# uARM.net
KiCad netlist of a schematic drawn in Altium Designer
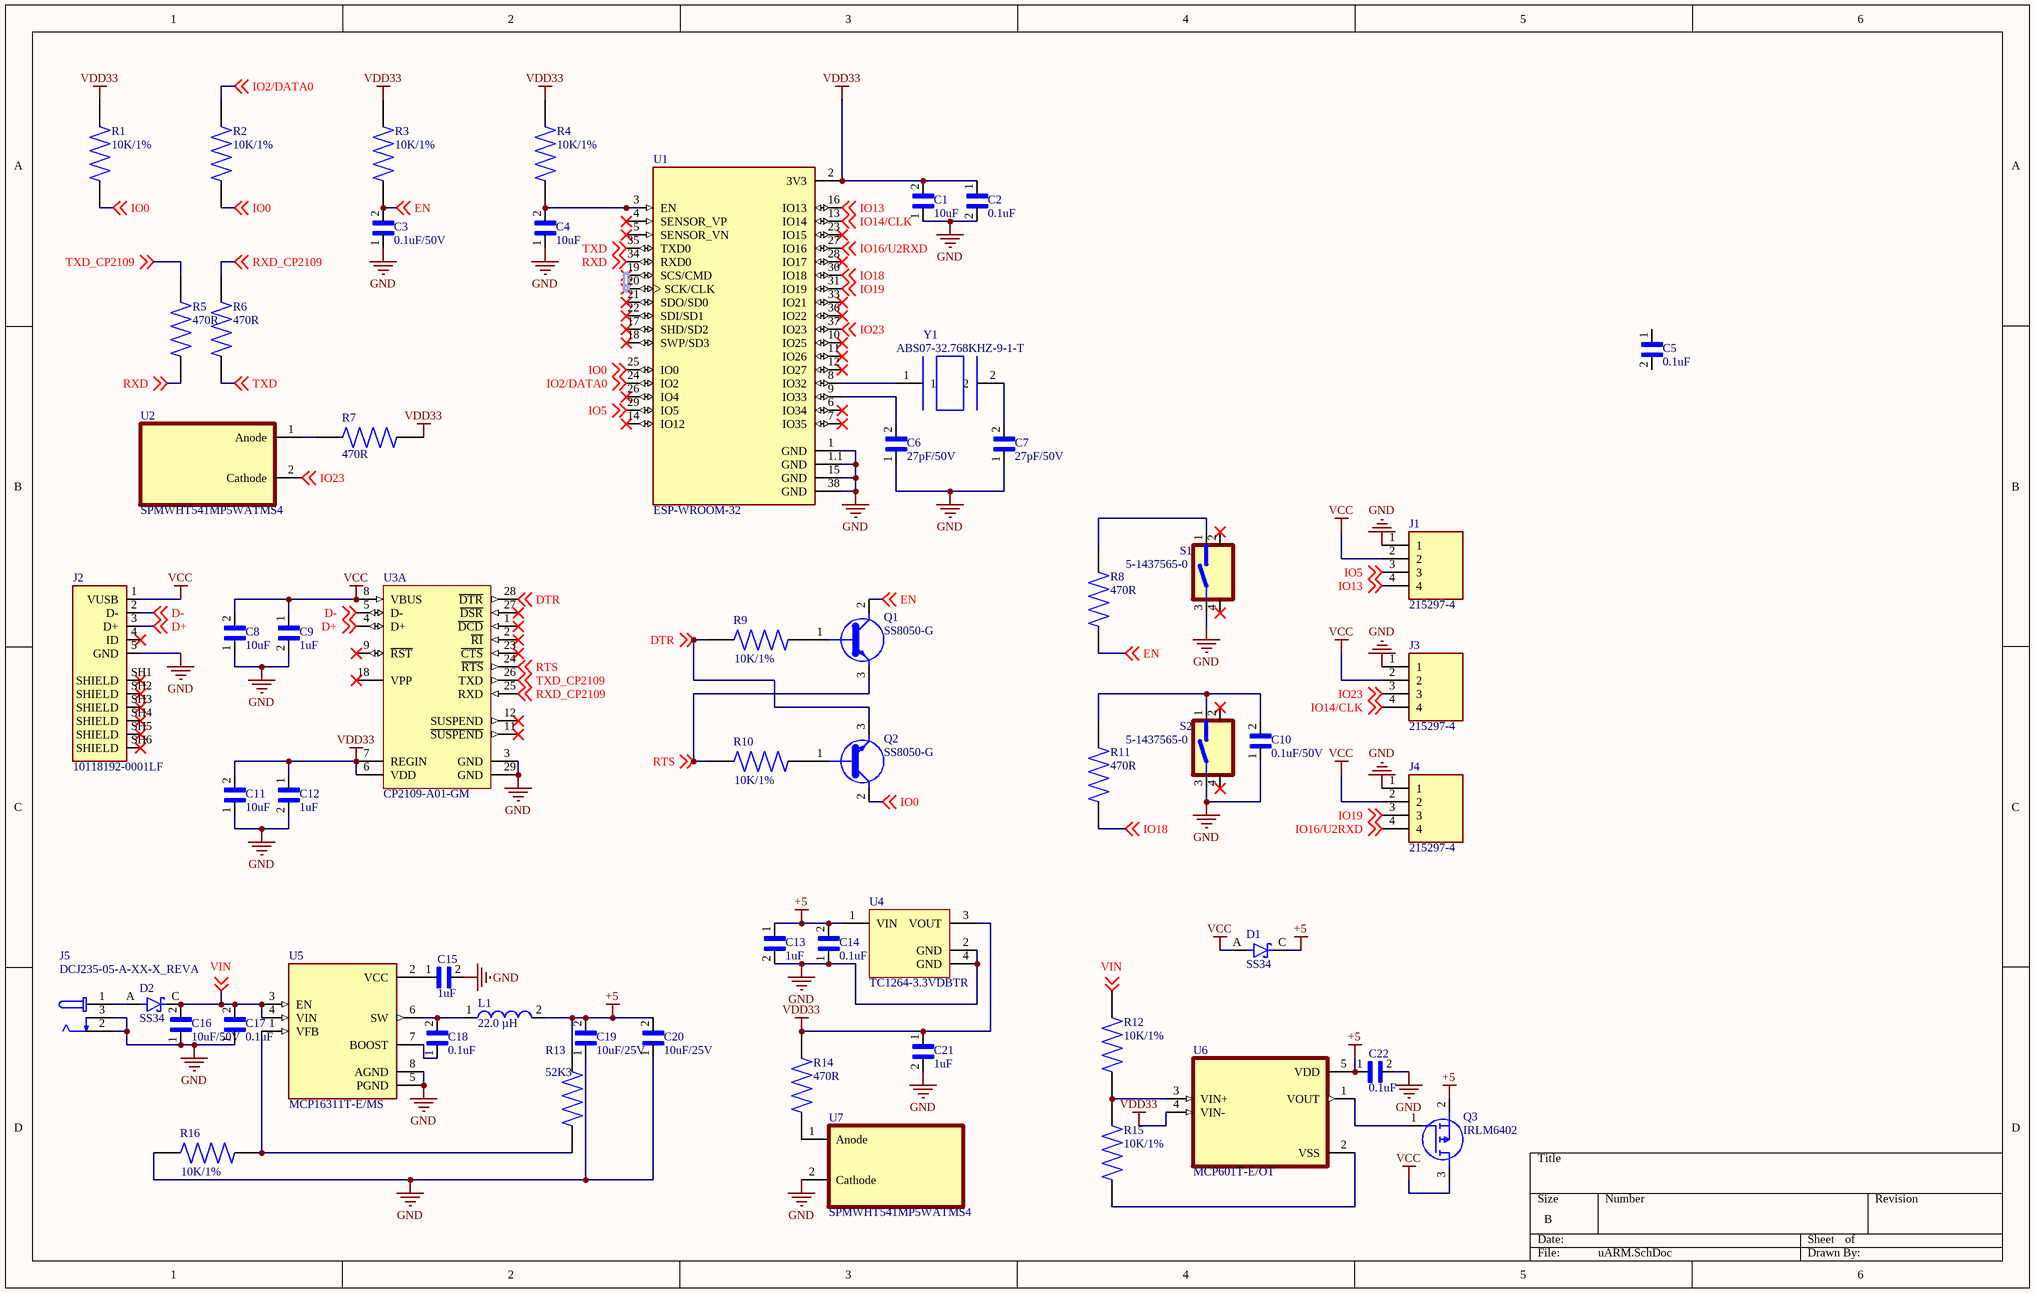
[diagram p0: uARM.SchDoc]

(export (version "E")
  (design (tool "Eeschema 10.0.6"))
  (components
    (comp (ref "C1")
      (value "10uF")
      (footprint "JMK212ABJ106KG-T:CAPC2012X140N")
      (description "CAP CER 10UF 6.3V X5R 0805")
      (fields (field (name "MP") "JMK212ABJ106KG-T") (field (name "MF") "{'manufacturer': u'Taiyo Yuden'}"))
      (libsource (lib "*") (part "JMK212ABJ106KG-T"))
    )
    (comp (ref "C2")
      (value "0.1uF")
      (footprint "08056D104KAT2A:CAPC2012X140N")
      (description "CAP 0.1UF 6.3VDC X5R 10% SMD 0805")
      (fields (field (name "MP") "08056D104KAT2A") (field (name "MF") "{'manufacturer': u'AVX'}"))
      (libsource (lib "") (part "08056D104KAT2A_2"))
    )
    (comp (ref "C3")
      (value "0.1uF/50V")
      (footprint "08055C104KAT4A:CAPC2012X94N")
      (description ".1UF 50V 10% 0805")
      (fields (field (name "MF") "{'manufacturer': u'AVX'}") (field (name "MP") "08055C104KAT4A"))
      (libsource (lib "*") (part "08055C104KAT4A"))
    )
    (comp (ref "C4")
      (value "10uF")
      (footprint "JMK212ABJ106KG-T:CAPC2012X140N")
      (description "CAP CER 10UF 6.3V X5R 0805")
      (fields (field (name "MP") "JMK212ABJ106KG-T") (field (name "MF") "{'manufacturer': u'Taiyo Yuden'}"))
      (libsource (lib "*") (part "JMK212ABJ106KG-T"))
    )
    (comp (ref "C5")
      (value "0.1uF")
      (footprint "08056D104KAT2A:CAPC2012X140N")
      (description "CAP 0.1UF 6.3VDC X5R 10% SMD 0805")
      (fields (field (name "MP") "08056D104KAT2A") (field (name "MF") "{'manufacturer': u'AVX'}"))
      (libsource (lib "") (part "08056D104KAT2A_2"))
    )
    (comp (ref "C6")
      (value "27pF/50V")
      (footprint "C0805C270J5GACTU:CAPC2012X88N")
      (fields (field (name "MP") "C0805C270J5GACTU") (field (name "MF") "{'manufacturer': u'KEMET'}"))
      (libsource (lib "*") (part "C0805C270J5GACTU"))
    )
    (comp (ref "C7")
      (value "27pF/50V")
      (footprint "C0805C270J5GACTU:CAPC2012X88N")
      (fields (field (name "MP") "C0805C270J5GACTU") (field (name "MF") "{'manufacturer': u'KEMET'}"))
      (libsource (lib "*") (part "C0805C270J5GACTU"))
    )
    (comp (ref "C8")
      (value "10uF")
      (footprint "JMK212ABJ106KG-T:CAPC2012X140N")
      (description "CAP CER 10UF 6.3V X5R 0805")
      (fields (field (name "MP") "JMK212ABJ106KG-T") (field (name "MF") "{'manufacturer': u'Taiyo Yuden'}"))
      (libsource (lib "*") (part "JMK212ABJ106KG-T"))
    )
    (comp (ref "C9")
      (value "1uF")
      (footprint "LGC26D105MAT2S1:CAPC2012X140N")
      (description "CAP CER 1UF 6.3V X5R 0805")
      (fields (field (name "MP") "LGC26D105MAT2S1") (field (name "MF") "{'manufacturer': u'AVX'}"))
      (libsource (lib "*") (part "LGC26D105MAT2S1"))
    )
    (comp (ref "C10")
      (value "0.1uF/50V")
      (footprint "08055C104KAT4A:CAPC2012X94N")
      (description ".1UF 50V 10% 0805")
      (fields (field (name "MF") "{'manufacturer': u'AVX'}") (field (name "MP") "08055C104KAT4A"))
      (libsource (lib "*") (part "08055C104KAT4A"))
    )
    (comp (ref "C11")
      (value "10uF")
      (footprint "JMK212ABJ106KG-T:CAPC2012X140N")
      (description "CAP CER 10UF 6.3V X5R 0805")
      (fields (field (name "MP") "JMK212ABJ106KG-T") (field (name "MF") "{'manufacturer': u'Taiyo Yuden'}"))
      (libsource (lib "*") (part "JMK212ABJ106KG-T"))
    )
    (comp (ref "C12")
      (value "1uF")
      (footprint "LGC26D105MAT2S1:CAPC2012X140N")
      (description "CAP CER 1UF 6.3V X5R 0805")
      (fields (field (name "MP") "LGC26D105MAT2S1") (field (name "MF") "{'manufacturer': u'AVX'}"))
      (libsource (lib "*") (part "LGC26D105MAT2S1"))
    )
    (comp (ref "C13")
      (value "1uF")
      (footprint "LGC26D105MAT2S1:CAPC2012X140N")
      (description "CAP CER 1UF 6.3V X5R 0805")
      (fields (field (name "MP") "LGC26D105MAT2S1") (field (name "MF") "{'manufacturer': u'AVX'}"))
      (libsource (lib "*") (part "LGC26D105MAT2S1"))
    )
    (comp (ref "C14")
      (value "0.1uF")
      (footprint "08056D104KAT2A:CAPC2012X140N")
      (description "CAP 0.1UF 6.3VDC X5R 10% SMD 0805")
      (fields (field (name "MP") "08056D104KAT2A") (field (name "MF") "{'manufacturer': u'AVX'}"))
      (libsource (lib "*") (part "08056D104KAT2A"))
    )
    (comp (ref "C15")
      (value "1uF")
      (footprint "LGC26D105MAT2S1:CAPC2012X140N")
      (description "CAP CER 1UF 6.3V X5R 0805")
      (fields (field (name "MP") "LGC26D105MAT2S1") (field (name "MF") "{'manufacturer': u'AVX'}"))
      (libsource (lib "") (part "LGC26D105MAT2S1_1"))
    )
    (comp (ref "C16")
      (value "10uF/50V")
      (footprint "GRM21BR61H106KE43L:CAPC2012X145N")
      (description "SMD Capacitor X5R(EIA) with Capacitance: 10uF Tol. 10%. Rated Voltage: 50Vdc")
      (fields
        (field (name "MP") "GRM21BR61H106KE43L")
        (field (name "MF") "{'manufacturer': u'Murata Electronics'}")
      )
      (libsource (lib "*") (part "GRM21BR61H106KE43L"))
    )
    (comp (ref "C17")
      (value "0.1uF")
      (footprint "08056D104KAT2A:CAPC2012X140N")
      (description "CAP 0.1UF 6.3VDC X5R 10% SMD 0805")
      (fields (field (name "MP") "08056D104KAT2A") (field (name "MF") "{'manufacturer': u'AVX'}"))
      (libsource (lib "*") (part "08056D104KAT2A"))
    )
    (comp (ref "C18")
      (value "0.1uF")
      (footprint "08056D104KAT2A:CAPC2012X140N")
      (description "CAP 0.1UF 6.3VDC X5R 10% SMD 0805")
      (fields (field (name "MP") "08056D104KAT2A") (field (name "MF") "{'manufacturer': u'AVX'}"))
      (libsource (lib "*") (part "08056D104KAT2A"))
    )
    (comp (ref "C19")
      (value "10uF/25V")
      (footprint "CL21A106KAYNNNE:CAPC2012X135N")
      (description "Cap Ceramic 10uF 25V X5R 10% SMD 0805 85Â°C Embossed T/R")
      (fields (field (name "MP") "CL21A106KAYNNNE") (field (name "MF") "{'manufacturer': u'Samsung'}"))
      (libsource (lib "*") (part "CL21A106KAYNNNE"))
    )
    (comp (ref "C20")
      (value "10uF/25V")
      (footprint "CL21A106KAYNNNE:CAPC2012X135N")
      (description "Cap Ceramic 10uF 25V X5R 10% SMD 0805 85Â°C Embossed T/R")
      (fields (field (name "MP") "CL21A106KAYNNNE") (field (name "MF") "{'manufacturer': u'Samsung'}"))
      (libsource (lib "*") (part "CL21A106KAYNNNE"))
    )
    (comp (ref "C21")
      (value "1uF")
      (footprint "LGC26D105MAT2S1:CAPC2012X140N")
      (description "CAP CER 1UF 6.3V X5R 0805")
      (fields (field (name "MP") "LGC26D105MAT2S1") (field (name "MF") "{'manufacturer': u'AVX'}"))
      (libsource (lib "*") (part "LGC26D105MAT2S1"))
    )
    (comp (ref "C22")
      (value "0.1uF")
      (footprint "08056D104KAT2A:CAPC2012X140N")
      (description "CAP 0.1UF 6.3VDC X5R 10% SMD 0805")
      (fields (field (name "MP") "08056D104KAT2A") (field (name "MF") "{'manufacturer': u'AVX'}"))
      (libsource (lib "") (part "08056D104KAT2A_1"))
    )
    (comp (ref "D1")
      (value "SS34")
      (footprint "SS34:DIOM7959X265N")
      (description "Diode Schottky 40V 3A 2-Pin SMC T/R")
      (fields (field (name "MF") "{'manufacturer': u'ON Semiconductor'}"))
      (libsource (lib "*") (part "SS34"))
    )
    (comp (ref "D2")
      (value "SS34")
      (footprint "SS34:DIOM7959X265N")
      (description "Diode Schottky 40V 3A 2-Pin SMC T/R")
      (fields (field (name "MF") "{'manufacturer': u'ON Semiconductor'}"))
      (libsource (lib "*") (part "SS34"))
    )
    (comp (ref "J1")
      (value "215297-4")
      (footprint "215297-4:TE_215297-4")
      (fields (field (name "MF") "{'manufacturer': u'TE Connectivity'}"))
      (libsource (lib "*") (part "215297-4"))
    )
    (comp (ref "J2")
      (value "10118192-0001LF")
      (footprint "10118192-0001LF:AMPHENOL_10118192-0001LF")
      (description "Single Port 5 Contact Horizontal Right Angle Shielded Micro B USB 2.0 Connector")
      (fields (field (name "MF") "{'manufacturer': u'FCI'}"))
      (libsource (lib "*") (part "10118192-0001LF"))
    )
    (comp (ref "J3")
      (value "215297-4")
      (footprint "215297-4:TE_215297-4")
      (fields (field (name "MF") "{'manufacturer': u'TE Connectivity'}"))
      (libsource (lib "*") (part "215297-4"))
    )
    (comp (ref "J4")
      (value "215297-4")
      (footprint "215297-4:TE_215297-4")
      (fields (field (name "MF") "{'manufacturer': u'TE Connectivity'}"))
      (libsource (lib "*") (part "215297-4"))
    )
    (comp (ref "J5")
      (value "DCJ235-05-A-XX-X_REVA")
      (footprint "DCJ235-05-A-K1-A:GCT_DCJ235-05-A-XX-X_REVA")
      (description "DC Power Jack, Thru-Hole, Horizontal, with Locating Pegs, D2.35mm")
      (fields (field (name "MF") "{'manufacturer': u'Global Connector Technology'}"))
      (libsource (lib "*") (part "DCJ235-05-A-XX-X_REVA"))
    )
    (comp (ref "L1")
      (value "744773122")
      (footprint "WE-PD2-S")
      (description "SMD Power Inductor WE-PD2, L = 22.0 µH")
      (fields (field (name "INDUCTANCE") "22.0 µH"))
      (libsource (lib "Wurth_Electronics_744773122") (part "744773122"))
    )
    (comp (ref "Q1")
      (value "SS8050-G")
      (footprint "SS8050-G:MBTB-T-SOT23")
      (fields (field (name "MF") "{'manufacturer': u'Comchip Technology'}"))
      (libsource (lib "*") (part "SS8050-G"))
    )
    (comp (ref "Q2")
      (value "SS8050-G")
      (footprint "SS8050-G:MBTB-T-SOT23")
      (fields (field (name "MF") "{'manufacturer': u'Comchip Technology'}"))
      (libsource (lib "*") (part "SS8050-G"))
    )
    (comp (ref "Q3")
      (value "IRLM6402")
      (footprint "SamacSys:SOT95P237X112-3N")
      (description "MOSFET (P-Channel)")
      (libsource (lib "*") (part "IRLM6402"))
    )
    (comp (ref "R1")
      (value "10K/1%")
      (footprint "ESR10EZPF1002:RESC2012X65N")
      (description "RES SMD 10K OHM 1% 0.4W 0805")
      (fields (field (name "MF") "{'manufacturer': u'Rohm'}") (field (name "MP") "ESR10EZPF1002"))
      (libsource (lib "*") (part "ESR10EZPF1002"))
    )
    (comp (ref "R2")
      (value "10K/1%")
      (footprint "ESR10EZPF1002:RESC2012X65N")
      (description "RES SMD 10K OHM 1% 0.4W 0805")
      (fields (field (name "MF") "{'manufacturer': u'Rohm'}") (field (name "MP") "ESR10EZPF1002"))
      (libsource (lib "*") (part "ESR10EZPF1002"))
    )
    (comp (ref "R3")
      (value "10K/1%")
      (footprint "ESR10EZPF1002:RESC2012X65N")
      (description "RES SMD 10K OHM 1% 0.4W 0805")
      (fields (field (name "MF") "{'manufacturer': u'Rohm'}") (field (name "MP") "ESR10EZPF1002"))
      (libsource (lib "*") (part "ESR10EZPF1002"))
    )
    (comp (ref "R4")
      (value "10K/1%")
      (footprint "ESR10EZPF1002:RESC2012X65N")
      (description "RES SMD 10K OHM 1% 0.4W 0805")
      (fields (field (name "MF") "{'manufacturer': u'Rohm'}") (field (name "MP") "ESR10EZPF1002"))
      (libsource (lib "*") (part "ESR10EZPF1002"))
    )
    (comp (ref "R5")
      (value "470R")
      (footprint "ERJ-PB6B4700V:RESC2012X70N")
      (fields (field (name "MP") "ERJ-PB6B4700V") (field (name "MF") "{'manufacturer': u'Panasonic'}"))
      (libsource (lib "*") (part "ERJ-PB6B4700V"))
    )
    (comp (ref "R6")
      (value "470R")
      (footprint "ERJ-PB6B4700V:RESC2012X70N")
      (fields (field (name "MP") "ERJ-PB6B4700V") (field (name "MF") "{'manufacturer': u'Panasonic'}"))
      (libsource (lib "*") (part "ERJ-PB6B4700V"))
    )
    (comp (ref "R7")
      (value "470R")
      (footprint "ERJ-PB6B4700V:RESC2012X70N")
      (fields (field (name "MP") "ERJ-PB6B4700V") (field (name "MF") "{'manufacturer': u'Panasonic'}"))
      (libsource (lib "*") (part "ERJ-PB6B4700V"))
    )
    (comp (ref "R8")
      (value "470R")
      (footprint "ERJ-PB6B4700V:RESC2012X70N")
      (fields (field (name "MP") "ERJ-PB6B4700V") (field (name "MF") "{'manufacturer': u'Panasonic'}"))
      (libsource (lib "*") (part "ERJ-PB6B4700V"))
    )
    (comp (ref "R9")
      (value "10K/1%")
      (footprint "ESR10EZPF1002:RESC2012X65N")
      (description "RES SMD 10K OHM 1% 0.4W 0805")
      (fields (field (name "MF") "{'manufacturer': u'Rohm'}") (field (name "MP") "ESR10EZPF1002"))
      (libsource (lib "*") (part "ESR10EZPF1002"))
    )
    (comp (ref "R10")
      (value "10K/1%")
      (footprint "ESR10EZPF1002:RESC2012X65N")
      (description "RES SMD 10K OHM 1% 0.4W 0805")
      (fields (field (name "MF") "{'manufacturer': u'Rohm'}") (field (name "MP") "ESR10EZPF1002"))
      (libsource (lib "*") (part "ESR10EZPF1002"))
    )
    (comp (ref "R11")
      (value "470R")
      (footprint "ERJ-PB6B4700V:RESC2012X70N")
      (fields (field (name "MP") "ERJ-PB6B4700V") (field (name "MF") "{'manufacturer': u'Panasonic'}"))
      (libsource (lib "*") (part "ERJ-PB6B4700V"))
    )
    (comp (ref "R12")
      (value "10K/1%")
      (footprint "ESR10EZPF1002:RESC2012X65N")
      (description "RES SMD 10K OHM 1% 0.4W 0805")
      (fields (field (name "MF") "{'manufacturer': u'Rohm'}") (field (name "MP") "ESR10EZPF1002"))
      (libsource (lib "*") (part "ESR10EZPF1002"))
    )
    (comp (ref "R13")
      (value "52K3")
      (footprint "ERJ-1GEF5232C:RESC0603X26N")
      (description "Res Thick Film 0201 52.3K Ohm 1% 0.05W(1/20W) Â±200ppm/C SMD T/R")
      (fields (field (name "MP") "ERJ-1GEF5232C") (field (name "MF") "{'manufacturer': u'Panasonic'}"))
      (libsource (lib "*") (part "ERJ-1GEF5232C"))
    )
    (comp (ref "R14")
      (value "470R")
      (footprint "ERJ-PB6B4700V:RESC2012X70N")
      (fields (field (name "MP") "ERJ-PB6B4700V") (field (name "MF") "{'manufacturer': u'Panasonic'}"))
      (libsource (lib "*") (part "ERJ-PB6B4700V"))
    )
    (comp (ref "R15")
      (value "10K/1%")
      (footprint "ESR10EZPF1002:RESC2012X65N")
      (description "RES SMD 10K OHM 1% 0.4W 0805")
      (fields (field (name "MF") "{'manufacturer': u'Rohm'}") (field (name "MP") "ESR10EZPF1002"))
      (libsource (lib "*") (part "ESR10EZPF1002"))
    )
    (comp (ref "R16")
      (value "10K/1%")
      (footprint "ESR10EZPF1002:RESC2012X65N")
      (description "RES SMD 10K OHM 1% 0.4W 0805")
      (fields (field (name "MF") "{'manufacturer': u'Rohm'}") (field (name "MP") "ESR10EZPF1002"))
      (libsource (lib "*") (part "ESR10EZPF1002"))
    )
    (comp (ref "S1")
      (value "5-1437565-0")
      (footprint "FSM6JSMATR:SW_5-1437565-0")
      (description "Switch Tactile OFF (ON) Round Button Gull Wing 0.05A 12VDC 1.57N SMD T/R")
      (fields (field (name "MF") "{'manufacturer': u'TE Connectivity'}"))
      (libsource (lib "*") (part "5-1437565-0"))
    )
    (comp (ref "S2")
      (value "5-1437565-0")
      (footprint "FSM6JSMATR:SW_5-1437565-0")
      (description "Switch Tactile OFF (ON) Round Button Gull Wing 0.05A 12VDC 1.57N SMD T/R")
      (fields (field (name "MF") "{'manufacturer': u'TE Connectivity'}"))
      (libsource (lib "*") (part "5-1437565-0"))
    )
    (comp (ref "U1")
      (value "ESP-WROOM-32")
      (footprint "ESP-WROOM-32:MODULE_ESP-WROOM-32")
      (description "Module: combo; GPIO, I2C x2, I2S x2, SDIO, SPI x3, UART x3; 19.5dBm")
      (fields (field (name "MF") "{'manufacturer': u'Espressif Systems'}"))
      (libsource (lib "*") (part "ESP-WROOM-32"))
    )
    (comp (ref "U2")
      (value "SPMWHT541MP5WATMS4")
      (footprint "LED_SPMWHT541MP5WAPKS4")
      (fields (field (name "MF") "{'manufacturer': u'Samsung Semiconductor,'}"))
      (libsource (lib "uARM") (part "SPMWHT541MP5WATMS4"))
    )
    (comp (ref "U3")
      (value "CP2109-A01-GM")
      (footprint "SLAB-QFN-28-3125x3125TP_L")
      (description "Single-Chip USB to UART Bridge, 1024 Bytes EEPROM, -40 to 85 degC, 28-pin QFN, Tube")
      (fields (field (name "MANUFACTURER") "Silicon Labs"))
      (libsource (lib "Silicon_Labs_CP2109_A01_GM") (part "CP2109-A01-GM"))
    )
    (comp (ref "U4")
      (value "TC1264-3.3VDBTR")
      (footprint "SOT-223-DB3_L")
      (description "800 mA Fixed-Output CMOS LDO with Shutdown, 3-Pin SOT-223, Extended Temperature, Tape and Reel")
      (libsource (lib "Microchip_TC1264_3_3VDBTR") (part "TC1264-3.3VDBTR"))
    )
    (comp (ref "U5")
      (value "MCP16311T-E/MS")
      (footprint "MCP16311T-E_MS:SOP65P490X110-8N")
      (fields (field (name "MF") "{'manufacturer': u'Microchip Technology'}"))
      (libsource (lib "*") (part "MCP16311T-E/MS"))
    )
    (comp (ref "U6")
      (value "MCP601T-E/OT")
      (footprint "MCP601T-E_OT:SOT95P270X145-5N")
      (fields (field (name "MF") "{'manufacturer': u'Microchip'}"))
      (libsource (lib "*") (part "MCP601T-E/OT"))
    )
    (comp (ref "U7")
      (value "SPMWHT541MP5WATMS4")
      (footprint "SPMWHT541MP5WATMS4:LED_SPMWHT541MP5WAPKS4")
      (fields (field (name "MF") "{'manufacturer': u'Samsung Semiconductor,'}"))
      (libsource (lib "*") (part "SPMWHT541MP5WATMS4"))
    )
    (comp (ref "Y1")
      (value "ABS07-32.768KHZ-9-1-T")
      (footprint "ABS07-32.768KHZ-9-1-T:XTAL320X150X90")
      (description "ABS07 Series 32.768 kHz Â±20 ppm 12.5 pF -40 to +85 C SMT Low Profile Crystal")
      (fields (field (name "MF") "{'manufacturer': u'Abracon'}"))
      (libsource (lib "*") (part "ABS07-32.768KHZ-9-1-T"))
    )
  )
  (nets
    (net (code "1") (name "+5") (class "Default")
      (node (ref "C13") (pin "1") (pinfunction "1_1") (pintype "passive"))
      (node (ref "C14") (pin "2") (pinfunction "2_2") (pintype "passive"))
      (node (ref "C19") (pin "2") (pinfunction "2_2") (pintype "passive"))
      (node (ref "C20") (pin "2") (pinfunction "2_2") (pintype "passive"))
      (node (ref "C22") (pin "1") (pinfunction "1_1") (pintype "passive"))
      (node (ref "D1") (pin "C") (pinfunction "K_C") (pintype "passive"))
      (node (ref "L1") (pin "2") (pinfunction "2_2") (pintype "passive"))
      (node (ref "Q3") (pin "2") (pinfunction "S_2") (pintype "passive"))
      (node (ref "R13") (pin "2") (pinfunction "2_2") (pintype "passive"))
      (node (ref "U4") (pin "1") (pinfunction "VIN_1") (pintype "power_in"))
      (node (ref "U6") (pin "5") (pinfunction "VDD_5") (pintype "power_in"))
    )
    (net (code "2") (name "D+") (class "Default")
      (node (ref "J2") (pin "3") (pinfunction "D+_3") (pintype "passive"))
      (node (ref "U3") (pin "4") (pinfunction "D+_4") (pintype "bidirectional"))
    )
    (net (code "3") (name "D-") (class "Default")
      (node (ref "J2") (pin "2") (pinfunction "D-_2") (pintype "passive"))
      (node (ref "U3") (pin "5") (pinfunction "D-_5") (pintype "bidirectional"))
    )
    (net (code "4") (name "DTR") (class "Default")
      (node (ref "Q2") (pin "3") (pinfunction "C_3") (pintype "bidirectional"))
      (node (ref "R9") (pin "1") (pinfunction "1_1") (pintype "passive"))
      (node (ref "U3") (pin "28") (pinfunction "~{DTR}_28") (pintype "output"))
    )
    (net (code "5") (name "EN") (class "Default")
      (node (ref "C3") (pin "2") (pinfunction "2_2") (pintype "passive"))
      (node (ref "Q1") (pin "2") (pinfunction "E_2") (pintype "bidirectional"))
      (node (ref "R3") (pin "1") (pinfunction "1_1") (pintype "passive"))
      (node (ref "R8") (pin "1") (pinfunction "1_1") (pintype "passive"))
    )
    (net (code "6") (name "GND") (class "Default")
      (node (ref "C1") (pin "1") (pinfunction "1_1") (pintype "passive"))
      (node (ref "C10") (pin "1") (pinfunction "1_1") (pintype "passive"))
      (node (ref "C11") (pin "1") (pinfunction "1_1") (pintype "passive"))
      (node (ref "C12") (pin "2") (pinfunction "2_2") (pintype "passive"))
      (node (ref "C13") (pin "2") (pinfunction "2_2") (pintype "passive"))
      (node (ref "C14") (pin "1") (pinfunction "1_1") (pintype "passive"))
      (node (ref "C15") (pin "2") (pinfunction "2_2") (pintype "passive"))
      (node (ref "C16") (pin "1") (pinfunction "1_1") (pintype "passive"))
      (node (ref "C17") (pin "1") (pinfunction "1_1") (pintype "passive"))
      (node (ref "C19") (pin "1") (pinfunction "1_1") (pintype "passive"))
      (node (ref "C2") (pin "2") (pinfunction "2_2") (pintype "passive"))
      (node (ref "C20") (pin "1") (pinfunction "1_1") (pintype "passive"))
      (node (ref "C21") (pin "2") (pinfunction "2_2") (pintype "passive"))
      (node (ref "C22") (pin "2") (pinfunction "2_2") (pintype "passive"))
      (node (ref "C3") (pin "1") (pinfunction "1_1") (pintype "passive"))
      (node (ref "C4") (pin "1") (pinfunction "1_1") (pintype "passive"))
      (node (ref "C6") (pin "1") (pinfunction "1_1") (pintype "passive"))
      (node (ref "C7") (pin "1") (pinfunction "1_1") (pintype "passive"))
      (node (ref "C8") (pin "1") (pinfunction "1_1") (pintype "passive"))
      (node (ref "C9") (pin "2") (pinfunction "2_2") (pintype "passive"))
      (node (ref "J1") (pin "1") (pinfunction "1_1") (pintype "passive"))
      (node (ref "J2") (pin "5") (pinfunction "GND_5") (pintype "passive"))
      (node (ref "J3") (pin "1") (pinfunction "1_1") (pintype "passive"))
      (node (ref "J4") (pin "1") (pinfunction "1_1") (pintype "passive"))
      (node (ref "J5") (pin "2") (pinfunction "2_2") (pintype "passive"))
      (node (ref "J5") (pin "3") (pinfunction "3_3") (pintype "passive"))
      (node (ref "R16") (pin "1") (pinfunction "1_1") (pintype "passive"))
      (node (ref "S1") (pin "3") (pinfunction "1_3") (pintype "passive"))
      (node (ref "S2") (pin "3") (pinfunction "1_3") (pintype "passive"))
      (node (ref "U1") (pin "1") (pinfunction "GND_1") (pintype "power_in"))
      (node (ref "U1") (pin "1.1") (pinfunction "GND_1.1") (pintype "power_in"))
      (node (ref "U1") (pin "15") (pinfunction "GND_15") (pintype "power_in"))
      (node (ref "U1") (pin "38") (pinfunction "GND_38") (pintype "power_in"))
      (node (ref "U3") (pin "29") (pinfunction "GND_29") (pintype "power_in"))
      (node (ref "U3") (pin "3") (pinfunction "GND_3") (pintype "power_in"))
      (node (ref "U4") (pin "2") (pinfunction "GND_2") (pintype "power_in"))
      (node (ref "U4") (pin "4") (pinfunction "GND_4") (pintype "power_in"))
      (node (ref "U5") (pin "5") (pinfunction "PGND_5") (pintype "power_in"))
      (node (ref "U5") (pin "8") (pinfunction "AGND_8") (pintype "power_in"))
      (node (ref "U7") (pin "2") (pinfunction "Cathode_2") (pintype "power_in"))
    )
    (net (code "7") (name "IO0") (class "Default")
      (node (ref "Q2") (pin "2") (pinfunction "E_2") (pintype "bidirectional"))
      (node (ref "R1") (pin "1") (pinfunction "1_1") (pintype "passive"))
      (node (ref "R2") (pin "1") (pinfunction "1_1") (pintype "passive"))
      (node (ref "U1") (pin "25") (pinfunction "IO0_25") (pintype "bidirectional"))
    )
    (net (code "8") (name "IO2{slash}DATA0") (class "Default")
      (node (ref "R2") (pin "2") (pinfunction "2_2") (pintype "passive"))
      (node (ref "U1") (pin "24") (pinfunction "IO2_24") (pintype "bidirectional"))
    )
    (net (code "9") (name "IO5") (class "Default")
      (node (ref "J1") (pin "3") (pinfunction "3_3") (pintype "passive"))
      (node (ref "U1") (pin "29") (pinfunction "IO5_29") (pintype "bidirectional"))
    )
    (net (code "10") (name "IO13") (class "Default")
      (node (ref "J1") (pin "4") (pinfunction "4_4") (pintype "passive"))
      (node (ref "U1") (pin "16") (pinfunction "IO13_16") (pintype "bidirectional"))
    )
    (net (code "11") (name "IO14{slash}CLK") (class "Default")
      (node (ref "J3") (pin "4") (pinfunction "4_4") (pintype "passive"))
      (node (ref "U1") (pin "13") (pinfunction "IO14_13") (pintype "bidirectional"))
    )
    (net (code "12") (name "IO16{slash}U2RXD") (class "Default")
      (node (ref "J4") (pin "4") (pinfunction "4_4") (pintype "passive"))
      (node (ref "U1") (pin "27") (pinfunction "IO16_27") (pintype "bidirectional"))
    )
    (net (code "13") (name "IO18") (class "Default")
      (node (ref "R11") (pin "1") (pinfunction "1_1") (pintype "passive"))
      (node (ref "U1") (pin "30") (pinfunction "IO18_30") (pintype "bidirectional"))
    )
    (net (code "14") (name "IO19") (class "Default")
      (node (ref "J4") (pin "3") (pinfunction "3_3") (pintype "passive"))
      (node (ref "U1") (pin "31") (pinfunction "IO19_31") (pintype "bidirectional"))
    )
    (net (code "15") (name "IO23") (class "Default")
      (node (ref "J3") (pin "3") (pinfunction "3_3") (pintype "passive"))
      (node (ref "U1") (pin "37") (pinfunction "IO23_37") (pintype "bidirectional"))
      (node (ref "U2") (pin "2") (pinfunction "Cathode_2") (pintype "power_in"))
    )
    (net (code "16") (name "Net-(C7-Pad2)") (class "Default")
      (node (ref "C7") (pin "2") (pinfunction "2_2") (pintype "passive"))
      (node (ref "Y1") (pin "2") (pinfunction "2_2") (pintype "passive"))
    )
    (net (code "17") (name "Net-(C10-Pad2)") (class "Default")
      (node (ref "C10") (pin "2") (pinfunction "2_2") (pintype "passive"))
      (node (ref "R11") (pin "2") (pinfunction "2_2") (pintype "passive"))
      (node (ref "S2") (pin "1") (pinfunction "2_1") (pintype "passive"))
    )
    (net (code "18") (name "Net-(D2-PadA)") (class "Default")
      (node (ref "D2") (pin "A") (pinfunction "A_A") (pintype "passive"))
      (node (ref "J5") (pin "1") (pinfunction "1_1") (pintype "passive"))
    )
    (net (code "19") (name "Net-(Q1-B)") (class "Default")
      (node (ref "Q1") (pin "1") (pinfunction "B_1") (pintype "bidirectional"))
      (node (ref "R9") (pin "2") (pinfunction "2_2") (pintype "passive"))
    )
    (net (code "20") (name "Net-(Q2-B)") (class "Default")
      (node (ref "Q2") (pin "1") (pinfunction "B_1") (pintype "bidirectional"))
      (node (ref "R10") (pin "2") (pinfunction "2_2") (pintype "passive"))
    )
    (net (code "21") (name "Net-(Q3-G)") (class "Default")
      (node (ref "Q3") (pin "1") (pinfunction "G_1") (pintype "passive"))
      (node (ref "U6") (pin "1") (pinfunction "VOUT_1") (pintype "output"))
    )
    (net (code "22") (name "Net-(R8-Pad2)") (class "Default")
      (node (ref "R8") (pin "2") (pinfunction "2_2") (pintype "passive"))
      (node (ref "S1") (pin "1") (pinfunction "2_1") (pintype "passive"))
    )
    (net (code "23") (name "Net-(U1-EN)") (class "Default")
      (node (ref "C4") (pin "2") (pinfunction "2_2") (pintype "passive"))
      (node (ref "R4") (pin "1") (pinfunction "1_1") (pintype "passive"))
      (node (ref "U1") (pin "3") (pinfunction "EN_3") (pintype "input"))
    )
    (net (code "24") (name "Net-(U1-IO32)") (class "Default")
      (node (ref "U1") (pin "8") (pinfunction "IO32_8") (pintype "bidirectional"))
      (node (ref "Y1") (pin "1") (pinfunction "1_1") (pintype "passive"))
    )
    (net (code "25") (name "Net-(U1-IO33)") (class "Default")
      (node (ref "C6") (pin "2") (pinfunction "2_2") (pintype "passive"))
      (node (ref "U1") (pin "9") (pinfunction "IO33_9") (pintype "bidirectional"))
    )
    (net (code "26") (name "Net-(U2-Anode)") (class "Default")
      (node (ref "R7") (pin "2") (pinfunction "2_2") (pintype "passive"))
      (node (ref "U2") (pin "1") (pinfunction "Anode_1") (pintype "power_in"))
    )
    (net (code "27") (name "Net-(U5-BOOST)") (class "Default")
      (node (ref "C18") (pin "1") (pinfunction "1_1") (pintype "passive"))
      (node (ref "U5") (pin "7") (pinfunction "BOOST_7") (pintype "passive"))
    )
    (net (code "28") (name "Net-(U5-SW)") (class "Default")
      (node (ref "C18") (pin "2") (pinfunction "2_2") (pintype "passive"))
      (node (ref "L1") (pin "1") (pinfunction "1_1") (pintype "passive"))
      (node (ref "U5") (pin "6") (pinfunction "SW_6") (pintype "output"))
    )
    (net (code "29") (name "Net-(U5-VCC)") (class "Default")
      (node (ref "C15") (pin "1") (pinfunction "1_1") (pintype "passive"))
      (node (ref "U5") (pin "2") (pinfunction "VCC_2") (pintype "power_in"))
    )
    (net (code "30") (name "Net-(U5-VFB)") (class "Default")
      (node (ref "R13") (pin "1") (pinfunction "1_1") (pintype "passive"))
      (node (ref "R16") (pin "2") (pinfunction "2_2") (pintype "passive"))
      (node (ref "U5") (pin "1") (pinfunction "VFB_1") (pintype "input"))
    )
    (net (code "31") (name "Net-(U6-VIN+)") (class "Default")
      (node (ref "R12") (pin "1") (pinfunction "1_1") (pintype "passive"))
      (node (ref "R15") (pin "2") (pinfunction "2_2") (pintype "passive"))
      (node (ref "U6") (pin "3") (pinfunction "VIN+_3") (pintype "input"))
    )
    (net (code "32") (name "Net-(U6-VSS)") (class "Default")
      (node (ref "R15") (pin "1") (pinfunction "1_1") (pintype "passive"))
      (node (ref "U6") (pin "2") (pinfunction "VSS_2") (pintype "power_in"))
    )
    (net (code "33") (name "Net-(U7-Anode)") (class "Default")
      (node (ref "R14") (pin "1") (pinfunction "1_1") (pintype "passive"))
      (node (ref "U7") (pin "1") (pinfunction "Anode_1") (pintype "power_in"))
    )
    (net (code "34") (name "RTS") (class "Default")
      (node (ref "Q1") (pin "3") (pinfunction "C_3") (pintype "bidirectional"))
      (node (ref "R10") (pin "1") (pinfunction "1_1") (pintype "passive"))
      (node (ref "U3") (pin "24") (pinfunction "~{RTS}_24") (pintype "output"))
    )
    (net (code "35") (name "RXD") (class "Default")
      (node (ref "R5") (pin "1") (pinfunction "1_1") (pintype "passive"))
      (node (ref "U1") (pin "34") (pinfunction "RXD0_34") (pintype "bidirectional"))
    )
    (net (code "36") (name "RXD_CP2109") (class "Default")
      (node (ref "R6") (pin "2") (pinfunction "2_2") (pintype "passive"))
      (node (ref "U3") (pin "25") (pinfunction "RXD_25") (pintype "input"))
    )
    (net (code "37") (name "TXD") (class "Default")
      (node (ref "R6") (pin "1") (pinfunction "1_1") (pintype "passive"))
      (node (ref "U1") (pin "35") (pinfunction "TXD0_35") (pintype "bidirectional"))
    )
    (net (code "38") (name "TXD_CP2109") (class "Default")
      (node (ref "R5") (pin "2") (pinfunction "2_2") (pintype "passive"))
      (node (ref "U3") (pin "26") (pinfunction "TXD_26") (pintype "output"))
    )
    (net (code "39") (name "VCC") (class "Default")
      (node (ref "C8") (pin "2") (pinfunction "2_2") (pintype "passive"))
      (node (ref "C9") (pin "1") (pinfunction "1_1") (pintype "passive"))
      (node (ref "D1") (pin "A") (pinfunction "A_A") (pintype "passive"))
      (node (ref "J1") (pin "2") (pinfunction "2_2") (pintype "passive"))
      (node (ref "J2") (pin "1") (pinfunction "VUSB_1") (pintype "passive"))
      (node (ref "J3") (pin "2") (pinfunction "2_2") (pintype "passive"))
      (node (ref "J4") (pin "2") (pinfunction "2_2") (pintype "passive"))
      (node (ref "Q3") (pin "3") (pinfunction "D_3") (pintype "passive"))
      (node (ref "U3") (pin "8") (pinfunction "VBUS_8") (pintype "input"))
    )
    (net (code "40") (name "VDD33") (class "Default")
      (node (ref "C1") (pin "2") (pinfunction "2_2") (pintype "passive"))
      (node (ref "C11") (pin "2") (pinfunction "2_2") (pintype "passive"))
      (node (ref "C12") (pin "1") (pinfunction "1_1") (pintype "passive"))
      (node (ref "C2") (pin "1") (pinfunction "1_1") (pintype "passive"))
      (node (ref "C21") (pin "1") (pinfunction "1_1") (pintype "passive"))
      (node (ref "R1") (pin "2") (pinfunction "2_2") (pintype "passive"))
      (node (ref "R14") (pin "2") (pinfunction "2_2") (pintype "passive"))
      (node (ref "R3") (pin "2") (pinfunction "2_2") (pintype "passive"))
      (node (ref "R4") (pin "2") (pinfunction "2_2") (pintype "passive"))
      (node (ref "R7") (pin "1") (pinfunction "1_1") (pintype "passive"))
      (node (ref "U1") (pin "2") (pinfunction "3V3_2") (pintype "power_in"))
      (node (ref "U3") (pin "6") (pinfunction "VDD_6") (pintype "power_in"))
      (node (ref "U3") (pin "7") (pinfunction "REGIN_7") (pintype "power_in"))
      (node (ref "U4") (pin "3") (pinfunction "VOUT_3") (pintype "power_in"))
      (node (ref "U6") (pin "4") (pinfunction "VIN-_4") (pintype "input"))
    )
    (net (code "41") (name "VIN") (class "Default")
      (node (ref "C16") (pin "2") (pinfunction "2_2") (pintype "passive"))
      (node (ref "C17") (pin "2") (pinfunction "2_2") (pintype "passive"))
      (node (ref "D2") (pin "C") (pinfunction "K_C") (pintype "passive"))
      (node (ref "R12") (pin "2") (pinfunction "2_2") (pintype "passive"))
      (node (ref "U5") (pin "3") (pinfunction "EN_3") (pintype "input"))
      (node (ref "U5") (pin "4") (pinfunction "VIN_4") (pintype "input"))
    )
    (net (code "42") (name "unconnected-(C5-Pad1)") (class "Default")
      (node (ref "C5") (pin "1") (pinfunction "1_1") (pintype "passive"))
    )
    (net (code "43") (name "unconnected-(C5-Pad2)") (class "Default")
      (node (ref "C5") (pin "2") (pinfunction "2_2") (pintype "passive"))
    )
    (net (code "44") (name "unconnected-(J2-ID-Pad4)") (class "Default")
      (node (ref "J2") (pin "4") (pinfunction "ID_4") (pintype "passive+no_connect"))
    )
    (net (code "45") (name "unconnected-(J2-SHIELD-PadSH1)") (class "Default")
      (node (ref "J2") (pin "SH1") (pinfunction "SHIELD_SH1") (pintype "passive+no_connect"))
    )
    (net (code "46") (name "unconnected-(J2-SHIELD-PadSH2)") (class "Default")
      (node (ref "J2") (pin "SH2") (pinfunction "SHIELD_SH2") (pintype "passive+no_connect"))
    )
    (net (code "47") (name "unconnected-(J2-SHIELD-PadSH3)") (class "Default")
      (node (ref "J2") (pin "SH3") (pinfunction "SHIELD_SH3") (pintype "passive+no_connect"))
    )
    (net (code "48") (name "unconnected-(J2-SHIELD-PadSH4)") (class "Default")
      (node (ref "J2") (pin "SH4") (pinfunction "SHIELD_SH4") (pintype "passive+no_connect"))
    )
    (net (code "49") (name "unconnected-(J2-SHIELD-PadSH5)") (class "Default")
      (node (ref "J2") (pin "SH5") (pinfunction "SHIELD_SH5") (pintype "passive+no_connect"))
    )
    (net (code "50") (name "unconnected-(J2-SHIELD-PadSH6)") (class "Default")
      (node (ref "J2") (pin "SH6") (pinfunction "SHIELD_SH6") (pintype "passive+no_connect"))
    )
    (net (code "51") (name "unconnected-(S1-1-Pad4)") (class "Default")
      (node (ref "S1") (pin "4") (pinfunction "1_4") (pintype "passive+no_connect"))
    )
    (net (code "52") (name "unconnected-(S1-Pad2)") (class "Default")
      (node (ref "S1") (pin "2") (pinfunction "2_2") (pintype "passive+no_connect"))
    )
    (net (code "53") (name "unconnected-(S2-1-Pad4)") (class "Default")
      (node (ref "S2") (pin "4") (pinfunction "1_4") (pintype "passive+no_connect"))
    )
    (net (code "54") (name "unconnected-(S2-Pad2)") (class "Default")
      (node (ref "S2") (pin "2") (pinfunction "2_2") (pintype "passive+no_connect"))
    )
    (net (code "55") (name "unconnected-(U1-IO4-Pad26)") (class "Default")
      (node (ref "U1") (pin "26") (pinfunction "IO4_26") (pintype "bidirectional+no_connect"))
    )
    (net (code "56") (name "unconnected-(U1-IO12-Pad14)") (class "Default")
      (node (ref "U1") (pin "14") (pinfunction "IO12_14") (pintype "bidirectional+no_connect"))
    )
    (net (code "57") (name "unconnected-(U1-IO15-Pad23)") (class "Default")
      (node (ref "U1") (pin "23") (pinfunction "IO15_23") (pintype "bidirectional+no_connect"))
    )
    (net (code "58") (name "unconnected-(U1-IO17-Pad28)") (class "Default")
      (node (ref "U1") (pin "28") (pinfunction "IO17_28") (pintype "bidirectional+no_connect"))
    )
    (net (code "59") (name "unconnected-(U1-IO21-Pad33)") (class "Default")
      (node (ref "U1") (pin "33") (pinfunction "IO21_33") (pintype "bidirectional+no_connect"))
    )
    (net (code "60") (name "unconnected-(U1-IO22-Pad36)") (class "Default")
      (node (ref "U1") (pin "36") (pinfunction "IO22_36") (pintype "bidirectional+no_connect"))
    )
    (net (code "61") (name "unconnected-(U1-IO25-Pad10)") (class "Default")
      (node (ref "U1") (pin "10") (pinfunction "IO25_10") (pintype "bidirectional+no_connect"))
    )
    (net (code "62") (name "unconnected-(U1-IO26-Pad11)") (class "Default")
      (node (ref "U1") (pin "11") (pinfunction "IO26_11") (pintype "bidirectional+no_connect"))
    )
    (net (code "63") (name "unconnected-(U1-IO27-Pad12)") (class "Default")
      (node (ref "U1") (pin "12") (pinfunction "IO27_12") (pintype "bidirectional+no_connect"))
    )
    (net (code "64") (name "unconnected-(U1-IO34-Pad6)") (class "Default")
      (node (ref "U1") (pin "6") (pinfunction "IO34_6") (pintype "bidirectional+no_connect"))
    )
    (net (code "65") (name "unconnected-(U1-IO35-Pad7)") (class "Default")
      (node (ref "U1") (pin "7") (pinfunction "IO35_7") (pintype "bidirectional+no_connect"))
    )
    (net (code "66") (name "unconnected-(U1-SCK{slash}CLK-Pad20)") (class "Default")
      (node (ref "U1") (pin "19") (pinfunction "SCS/CMD_19") (pintype "bidirectional"))
      (node (ref "U1") (pin "20") (pinfunction "SCK/CLK_20") (pintype "bidirectional"))
    )
    (net (code "67") (name "unconnected-(U1-SDI{slash}SD1-Pad22)") (class "Default")
      (node (ref "U1") (pin "22") (pinfunction "SDI/SD1_22") (pintype "bidirectional+no_connect"))
    )
    (net (code "68") (name "unconnected-(U1-SDO{slash}SD0-Pad21)") (class "Default")
      (node (ref "U1") (pin "21") (pinfunction "SDO/SD0_21") (pintype "bidirectional+no_connect"))
    )
    (net (code "69") (name "unconnected-(U1-SENSOR_VN-Pad5)") (class "Default")
      (node (ref "U1") (pin "5") (pinfunction "SENSOR_VN_5") (pintype "input+no_connect"))
    )
    (net (code "70") (name "unconnected-(U1-SENSOR_VP-Pad4)") (class "Default")
      (node (ref "U1") (pin "4") (pinfunction "SENSOR_VP_4") (pintype "input+no_connect"))
    )
    (net (code "71") (name "unconnected-(U1-SHD{slash}SD2-Pad17)") (class "Default")
      (node (ref "U1") (pin "17") (pinfunction "SHD/SD2_17") (pintype "bidirectional+no_connect"))
    )
    (net (code "72") (name "unconnected-(U1-SWP{slash}SD3-Pad18)") (class "Default")
      (node (ref "U1") (pin "18") (pinfunction "SWP/SD3_18") (pintype "bidirectional+no_connect"))
    )
    (net (code "73") (name "unconnected-(U3A-SUSPEND-Pad12)") (class "Default")
      (node (ref "U3") (pin "12") (pinfunction "SUSPEND_12") (pintype "output+no_connect"))
    )
    (net (code "74") (name "unconnected-(U3A-VPP-Pad18)") (class "Default")
      (node (ref "U3") (pin "18") (pinfunction "VPP_18") (pintype "passive+no_connect"))
    )
    (net (code "75") (name "unconnected-(U3A-~{CTS}-Pad23)") (class "Default")
      (node (ref "U3") (pin "23") (pinfunction "~{CTS}_23") (pintype "input+no_connect"))
    )
    (net (code "76") (name "unconnected-(U3A-~{DCD}-Pad1)") (class "Default")
      (node (ref "U3") (pin "1") (pinfunction "~{DCD}_1") (pintype "input+no_connect"))
    )
    (net (code "77") (name "unconnected-(U3A-~{DSR}-Pad27)") (class "Default")
      (node (ref "U3") (pin "27") (pinfunction "~{DSR}_27") (pintype "input+no_connect"))
    )
    (net (code "78") (name "unconnected-(U3A-~{RI}-Pad2)") (class "Default")
      (node (ref "U3") (pin "2") (pinfunction "~{RI}_2") (pintype "input+no_connect"))
    )
    (net (code "79") (name "unconnected-(U3A-~{RST}-Pad9)") (class "Default")
      (node (ref "U3") (pin "9") (pinfunction "~{RST}_9") (pintype "bidirectional+no_connect"))
    )
    (net (code "80") (name "unconnected-(U3A-~{SUSPEND}-Pad11)") (class "Default")
      (node (ref "U3") (pin "11") (pinfunction "~{SUSPEND}_11") (pintype "output+no_connect"))
    )
  )
)
